# sensor.net
KiCad netlist of a schematic drawn in EAGLE
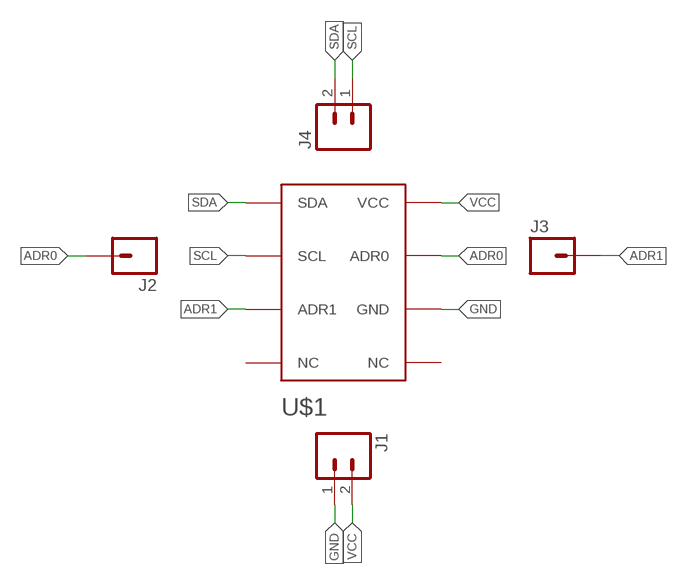
[diagram p0: schematic, sheet 1]

(export (version "E")
  (design (tool "Eeschema 10.0.6"))
  (components
    (comp (ref "J1")
      (value "M02PTH")
      (footprint "eagle-import:1X02")
      (libsource (lib "eagle-import") (part "M02PTH"))
    )
    (comp (ref "J2")
      (value "M01PTH")
      (footprint "eagle-import:1X01")
      (libsource (lib "eagle-import") (part "M01PTH"))
    )
    (comp (ref "J3")
      (value "M01PTH")
      (footprint "eagle-import:1X01")
      (libsource (lib "eagle-import") (part "M01PTH"))
    )
    (comp (ref "J4")
      (value "M02PTH")
      (footprint "eagle-import:1X02")
      (libsource (lib "eagle-import") (part "M02PTH"))
    )
    (comp (ref "U$1")
      (value "A1454")
      (footprint "eagle-import:TSSOP8")
      (libsource (lib "eagle-import") (part "A1454"))
    )
  )
  (nets
    (net (code "1") (name "ADR0") (class "Default")
      (node (ref "J2") (pin "1") (pinfunction "1_1") (pintype "passive"))
      (node (ref "U$1") (pin "2") (pinfunction "ADR0_2") (pintype "bidirectional"))
    )
    (net (code "2") (name "ADR1") (class "Default")
      (node (ref "J3") (pin "1") (pinfunction "1_1") (pintype "passive"))
      (node (ref "U$1") (pin "6") (pinfunction "ADR1_6") (pintype "bidirectional"))
    )
    (net (code "3") (name "GND") (class "Default")
      (node (ref "J1") (pin "1") (pinfunction "1_1") (pintype "passive"))
      (node (ref "U$1") (pin "3") (pinfunction "GND_3") (pintype "bidirectional"))
    )
    (net (code "4") (name "SCL") (class "Default")
      (node (ref "J4") (pin "1") (pinfunction "1_1") (pintype "passive"))
      (node (ref "U$1") (pin "8") (pinfunction "SCL_8") (pintype "bidirectional"))
    )
    (net (code "5") (name "SDA") (class "Default")
      (node (ref "J4") (pin "2") (pinfunction "2_2") (pintype "passive"))
      (node (ref "U$1") (pin "7") (pinfunction "SDA_7") (pintype "bidirectional"))
    )
    (net (code "6") (name "VCC") (class "Default")
      (node (ref "J1") (pin "2") (pinfunction "2_2") (pintype "passive"))
      (node (ref "U$1") (pin "1") (pinfunction "VCC_1") (pintype "bidirectional"))
    )
    (net (code "7") (name "unconnected-(U$1-NC-Pad4)") (class "Default")
      (node (ref "U$1") (pin "4") (pinfunction "NC_4") (pintype "bidirectional"))
    )
    (net (code "8") (name "unconnected-(U$1-NC-Pad5)") (class "Default")
      (node (ref "U$1") (pin "5") (pinfunction "NC_5") (pintype "bidirectional"))
    )
  )
)
